# ProPrj___2024-07-22_15-28-46_2024-09-27.net
KiCad netlist of a schematic drawn in EasyEDA Pro
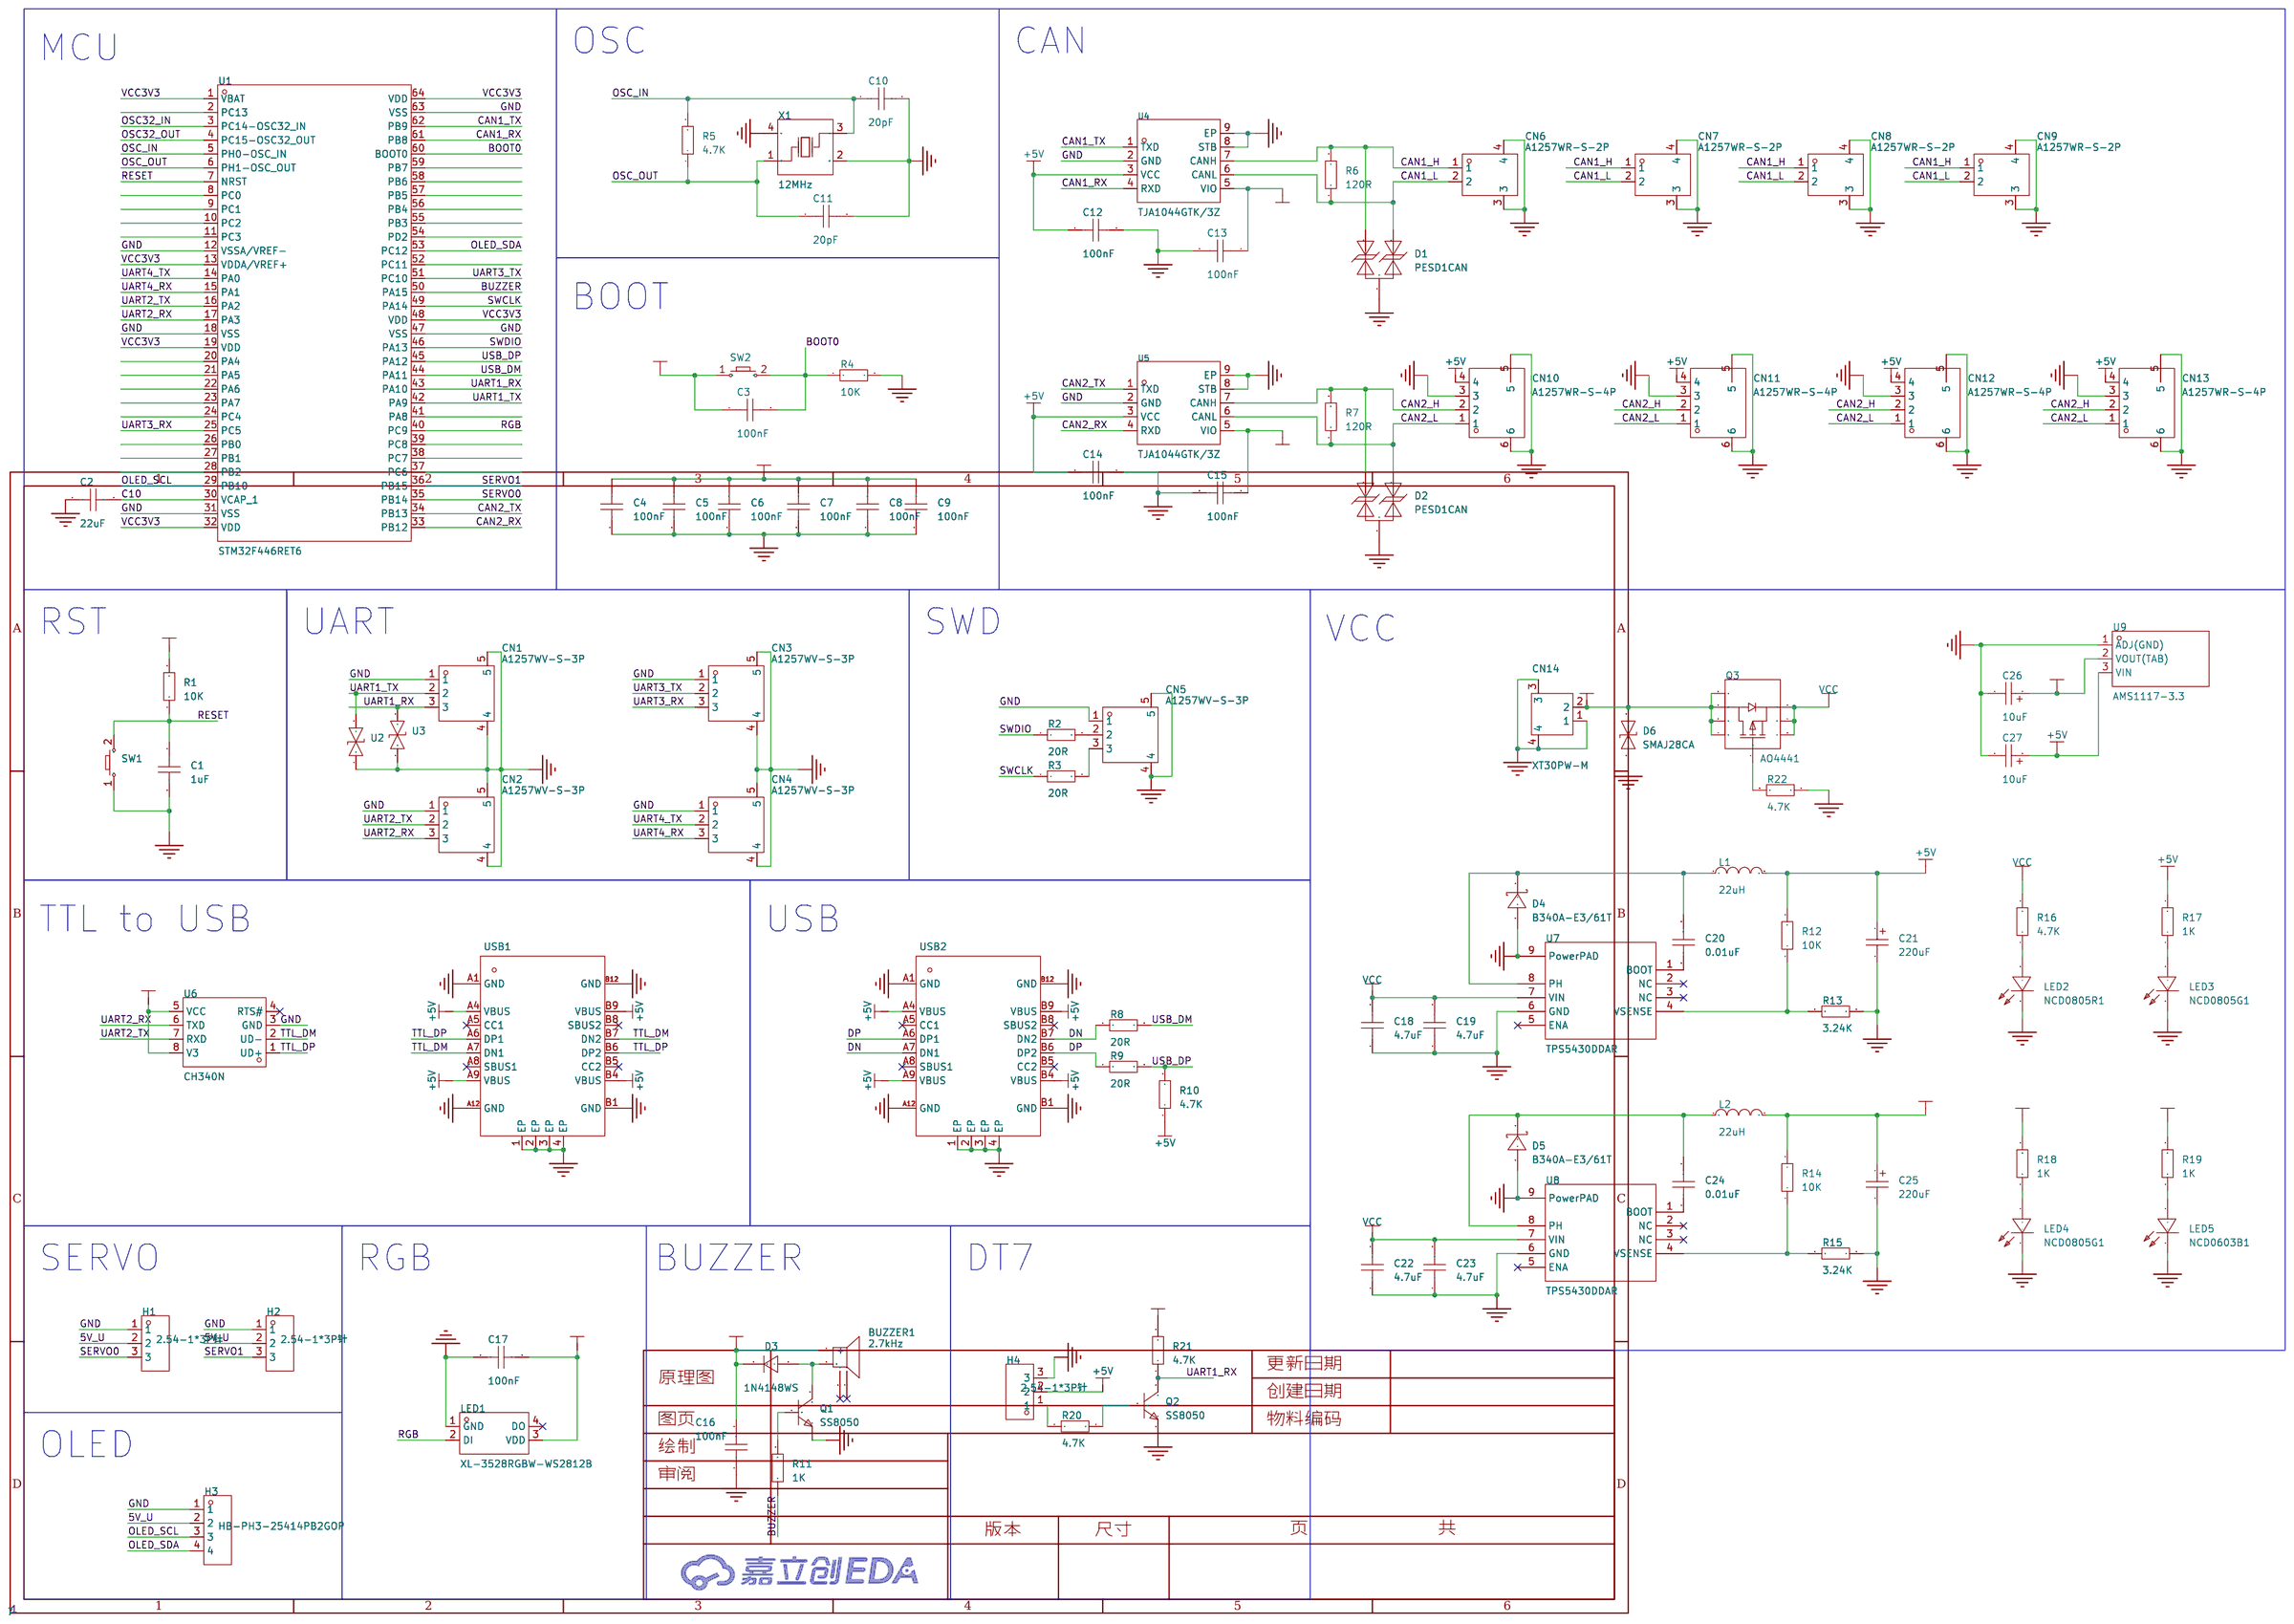
[diagram p0: schematic sheet]

(export (version "E")
  (design (tool "Eeschema 10.0.6"))
  (components
    (comp (ref "BUZZER1")
      (value "2.7kHz")
      (footprint "easyedapro:BUZ-SMD_4P-L8.5-W8.5-P8.50-BR")
      (description "驱动方式:无源(外部驱动);构造类型:电磁式;频率:2.7kHz;声压(SPL):80dB@5V,10cm;")
      (fields (field (name "Manufacturer Part") "MLT-8530") (field (name "Manufacturer") "华能"))
      (libsource (lib "easyedapro") (part "MLT-8530"))
    )
    (comp (ref "C1")
      (value "1uF")
      (footprint "easyedapro:C0603")
      (libsource (lib "easyedapro") (part "CapAcitance"))
    )
    (comp (ref "C2")
      (value "22uF")
      (footprint "easyedapro:C0603")
      (libsource (lib "easyedapro") (part "CapAcitance"))
    )
    (comp (ref "C3")
      (value "100nF")
      (footprint "easyedapro:C0603")
      (libsource (lib "easyedapro") (part "CapAcitance"))
    )
    (comp (ref "C4")
      (value "100nF")
      (footprint "easyedapro:C0603")
      (libsource (lib "easyedapro") (part "CapAcitance"))
    )
    (comp (ref "C5")
      (value "100nF")
      (footprint "easyedapro:C0603")
      (libsource (lib "easyedapro") (part "CapAcitance"))
    )
    (comp (ref "C6")
      (value "100nF")
      (footprint "easyedapro:C0603")
      (libsource (lib "easyedapro") (part "CapAcitance"))
    )
    (comp (ref "C7")
      (value "100nF")
      (footprint "easyedapro:C0603")
      (libsource (lib "easyedapro") (part "CapAcitance"))
    )
    (comp (ref "C8")
      (value "100nF")
      (footprint "easyedapro:C0603")
      (libsource (lib "easyedapro") (part "CapAcitance"))
    )
    (comp (ref "C9")
      (value "100nF")
      (footprint "easyedapro:C0603")
      (libsource (lib "easyedapro") (part "CapAcitance"))
    )
    (comp (ref "C10")
      (value "20pF")
      (footprint "easyedapro:C0603")
      (libsource (lib "easyedapro") (part "CapAcitance"))
    )
    (comp (ref "C11")
      (value "20pF")
      (footprint "easyedapro:C0603")
      (libsource (lib "easyedapro") (part "CapAcitance"))
    )
    (comp (ref "C12")
      (value "100nF")
      (footprint "easyedapro:C0603")
      (libsource (lib "easyedapro") (part "CapAcitance"))
    )
    (comp (ref "C13")
      (value "100nF")
      (footprint "easyedapro:C0603")
      (libsource (lib "easyedapro") (part "CapAcitance"))
    )
    (comp (ref "C14")
      (value "100nF")
      (footprint "easyedapro:C0603")
      (libsource (lib "easyedapro") (part "CapAcitance"))
    )
    (comp (ref "C15")
      (value "100nF")
      (footprint "easyedapro:C0603")
      (libsource (lib "easyedapro") (part "CapAcitance"))
    )
    (comp (ref "C16")
      (value "100nF")
      (footprint "easyedapro:C0603")
      (libsource (lib "easyedapro") (part "CapAcitance"))
    )
    (comp (ref "C17")
      (value "100nF")
      (footprint "easyedapro:C0603")
      (libsource (lib "easyedapro") (part "CapAcitance"))
    )
    (comp (ref "C18")
      (value "4.7uF")
      (footprint "easyedapro:C0603")
      (libsource (lib "easyedapro") (part "CapAcitance"))
    )
    (comp (ref "C19")
      (value "4.7uF")
      (footprint "easyedapro:C0603")
      (libsource (lib "easyedapro") (part "CapAcitance"))
    )
    (comp (ref "C20")
      (value "0.01uF")
      (footprint "easyedapro:C0603")
      (libsource (lib "easyedapro") (part "CapAcitance"))
    )
    (comp (ref "C21")
      (value "220uF")
      (footprint "easyedapro:C_Ele_SMD_5x5.4mm")
      (libsource (lib "easyedapro") (part "CAP"))
    )
    (comp (ref "C22")
      (value "4.7uF")
      (footprint "easyedapro:C0603")
      (libsource (lib "easyedapro") (part "CapAcitance"))
    )
    (comp (ref "C23")
      (value "4.7uF")
      (footprint "easyedapro:C0603")
      (libsource (lib "easyedapro") (part "CapAcitance"))
    )
    (comp (ref "C24")
      (value "0.01uF")
      (footprint "easyedapro:C0603")
      (libsource (lib "easyedapro") (part "CapAcitance"))
    )
    (comp (ref "C25")
      (value "220uF")
      (footprint "easyedapro:C_Ele_SMD_5x5.4mm")
      (libsource (lib "easyedapro") (part "CAP"))
    )
    (comp (ref "C26")
      (value "10uF")
      (footprint "easyedapro:C_Ele_SMD_5x5.4mm")
      (libsource (lib "easyedapro") (part "CAP"))
    )
    (comp (ref "C27")
      (value "10uF")
      (footprint "easyedapro:C_Ele_SMD_5x5.4mm")
      (libsource (lib "easyedapro") (part "CAP"))
    )
    (comp (ref "CN1")
      (value "A1257WV-S-3P")
      (footprint "easyedapro:CONN-SMD_A1257WV-S-3P")
      (description "插针结构:1x3P;间距:1.25mm;安装方式:-;参考系列:GH;总PIN数:3P;排数:1;每排PIN数:3;行距:-;触头材质:黄铜;")
      (fields (field (name "Manufacturer") "CJT(长江连接器)"))
      (libsource (lib "easyedapro") (part "A1257WV-S-3P"))
    )
    (comp (ref "CN2")
      (value "A1257WV-S-3P")
      (footprint "easyedapro:CONN-SMD_A1257WV-S-3P")
      (description "插针结构:1x3P;间距:1.25mm;安装方式:-;参考系列:GH;总PIN数:3P;排数:1;每排PIN数:3;行距:-;触头材质:黄铜;")
      (fields (field (name "Manufacturer") "CJT(长江连接器)"))
      (libsource (lib "easyedapro") (part "A1257WV-S-3P"))
    )
    (comp (ref "CN3")
      (value "A1257WV-S-3P")
      (footprint "easyedapro:CONN-SMD_A1257WV-S-3P")
      (description "插针结构:1x3P;间距:1.25mm;安装方式:-;参考系列:GH;总PIN数:3P;排数:1;每排PIN数:3;行距:-;触头材质:黄铜;")
      (fields (field (name "Manufacturer") "CJT(长江连接器)"))
      (libsource (lib "easyedapro") (part "A1257WV-S-3P"))
    )
    (comp (ref "CN4")
      (value "A1257WV-S-3P")
      (footprint "easyedapro:CONN-SMD_A1257WV-S-3P")
      (description "插针结构:1x3P;间距:1.25mm;安装方式:-;参考系列:GH;总PIN数:3P;排数:1;每排PIN数:3;行距:-;触头材质:黄铜;")
      (fields (field (name "Manufacturer") "CJT(长江连接器)"))
      (libsource (lib "easyedapro") (part "A1257WV-S-3P"))
    )
    (comp (ref "CN5")
      (value "A1257WV-S-3P")
      (footprint "easyedapro:CONN-SMD_A1257WV-S-3P")
      (description "插针结构:1x3P;间距:1.25mm;安装方式:-;参考系列:GH;总PIN数:3P;排数:1;每排PIN数:3;行距:-;触头材质:黄铜;")
      (fields (field (name "Manufacturer") "CJT(长江连接器)"))
      (libsource (lib "easyedapro") (part "A1257WV-S-3P"))
    )
    (comp (ref "CN6")
      (value "A1257WR-S-2P")
      (footprint "easyedapro:CONN-SMD_A1257WR-S-2P")
      (description "插针结构:1x2P;间距:1.25mm;安装方式:-;参考系列:GH;总PIN数:2P;排数:1;每排PIN数:2;行距:-;触头材质:黄铜;")
      (fields (field (name "Manufacturer") "CJT(长江连接器)"))
      (libsource (lib "easyedapro") (part "A1257WR-S-2P"))
    )
    (comp (ref "CN7")
      (value "A1257WR-S-2P")
      (footprint "easyedapro:CONN-SMD_A1257WR-S-2P")
      (description "插针结构:1x2P;间距:1.25mm;安装方式:-;参考系列:GH;总PIN数:2P;排数:1;每排PIN数:2;行距:-;触头材质:黄铜;")
      (fields (field (name "Manufacturer") "CJT(长江连接器)"))
      (libsource (lib "easyedapro") (part "A1257WR-S-2P"))
    )
    (comp (ref "CN8")
      (value "A1257WR-S-2P")
      (footprint "easyedapro:CONN-SMD_A1257WR-S-2P")
      (description "插针结构:1x2P;间距:1.25mm;安装方式:-;参考系列:GH;总PIN数:2P;排数:1;每排PIN数:2;行距:-;触头材质:黄铜;")
      (fields (field (name "Manufacturer") "CJT(长江连接器)"))
      (libsource (lib "easyedapro") (part "A1257WR-S-2P"))
    )
    (comp (ref "CN9")
      (value "A1257WR-S-2P")
      (footprint "easyedapro:CONN-SMD_A1257WR-S-2P")
      (description "插针结构:1x2P;间距:1.25mm;安装方式:-;参考系列:GH;总PIN数:2P;排数:1;每排PIN数:2;行距:-;触头材质:黄铜;")
      (fields (field (name "Manufacturer") "CJT(长江连接器)"))
      (libsource (lib "easyedapro") (part "A1257WR-S-2P"))
    )
    (comp (ref "CN10")
      (value "A1257WR-S-4P")
      (footprint "easyedapro:CONN-SMD_A1257WR-S-4P")
      (description "插针结构:1x4P;间距:1.25mm;安装方式:-;参考系列:GH;总PIN数:4P;排数:1;每排PIN数:4;行距:-;触头材质:黄铜;")
      (fields (field (name "Manufacturer") "CJT(长江连接器)"))
      (libsource (lib "easyedapro") (part "A1257WR-S-4P"))
    )
    (comp (ref "CN11")
      (value "A1257WR-S-4P")
      (footprint "easyedapro:CONN-SMD_A1257WR-S-4P")
      (description "插针结构:1x4P;间距:1.25mm;安装方式:-;参考系列:GH;总PIN数:4P;排数:1;每排PIN数:4;行距:-;触头材质:黄铜;")
      (fields (field (name "Manufacturer") "CJT(长江连接器)"))
      (libsource (lib "easyedapro") (part "A1257WR-S-4P"))
    )
    (comp (ref "CN12")
      (value "A1257WR-S-4P")
      (footprint "easyedapro:CONN-SMD_A1257WR-S-4P")
      (description "插针结构:1x4P;间距:1.25mm;安装方式:-;参考系列:GH;总PIN数:4P;排数:1;每排PIN数:4;行距:-;触头材质:黄铜;")
      (fields (field (name "Manufacturer") "CJT(长江连接器)"))
      (libsource (lib "easyedapro") (part "A1257WR-S-4P"))
    )
    (comp (ref "CN13")
      (value "A1257WR-S-4P")
      (footprint "easyedapro:CONN-SMD_A1257WR-S-4P")
      (description "插针结构:1x4P;间距:1.25mm;安装方式:-;参考系列:GH;总PIN数:4P;排数:1;每排PIN数:4;行距:-;触头材质:黄铜;")
      (fields (field (name "Manufacturer") "CJT(长江连接器)"))
      (libsource (lib "easyedapro") (part "A1257WR-S-4P"))
    )
    (comp (ref "CN14")
      (value "XT30PW-M")
      (footprint "easyedapro:CONN-TH_XT30PW-M")
      (description "类别:-;类型1:-;")
      (fields (field (name "Manufacturer") "AMASS(艾迈斯)"))
      (libsource (lib "easyedapro") (part "XT30PW-M"))
    )
    (comp (ref "D1")
      (value "PESD1CAN")
      (footprint "easyedapro:SOT-23-3_L2.9-W1.6-P1.90-LS2.8-BR")
      (description "极性:双向;反向截止电压(Vrwm):24V;最大钳位电压:48V;峰值脉冲电流(Ipp)@10/1000us:6A;击穿电压:26.7V;")
      (fields (field (name "Manufacturer") "BORN(伯恩半导体)"))
      (libsource (lib "easyedapro") (part "PESD1CAN_C343993"))
    )
    (comp (ref "D2")
      (value "PESD1CAN")
      (footprint "easyedapro:SOT-23-3_L2.9-W1.6-P1.90-LS2.8-BR")
      (description "极性:双向;反向截止电压(Vrwm):24V;最大钳位电压:48V;峰值脉冲电流(Ipp)@10/1000us:6A;击穿电压:26.7V;")
      (fields (field (name "Manufacturer") "BORN(伯恩半导体)"))
      (libsource (lib "easyedapro") (part "PESD1CAN_C343993"))
    )
    (comp (ref "D3")
      (value "1N4148WS")
      (footprint "easyedapro:SOD-323_L1.8-W1.3-LS2.5-RD")
      (description "二极管配置:独立式;正向压降(Vf):1.25V@150mA;直流反向耐压(Vr):100V;平均整流电流(Io):150mA;功率:200mW;反向恢复时间(trr):4ns;")
      (fields (field (name "Manufacturer") "CJ(江苏长电/长晶)"))
      (libsource (lib "easyedapro") (part "1N4148WS T4"))
    )
    (comp (ref "D4")
      (value "B340A-E3/61T")
      (footprint "easyedapro:SMA_L4.3-W2.6-LS5.2-RD")
      (description "正向压降(Vf):550mV@3A;直流反向耐压(Vr):40V;平均整流电流(Io):3A;")
      (fields (field (name "Manufacturer") "VISHAY(威世)"))
      (libsource (lib "easyedapro") (part "B340A-E3/61T"))
    )
    (comp (ref "D5")
      (value "B340A-E3/61T")
      (footprint "easyedapro:SMA_L4.3-W2.6-LS5.2-RD")
      (description "正向压降(Vf):550mV@3A;直流反向耐压(Vr):40V;平均整流电流(Io):3A;")
      (fields (field (name "Manufacturer") "VISHAY(威世)"))
      (libsource (lib "easyedapro") (part "B340A-E3/61T"))
    )
    (comp (ref "D6")
      (value "SMAJ28CA")
      (footprint "easyedapro:SMA_L4.4-W2.6-LS5.0-BI")
      (description "反向截止电压(Vrwm):28V;最大钳位电压:45.4V;峰值脉冲电流(Ipp)@10/1000us:8.8A;峰值脉冲功率(Ppp)@10/1000us:400W;击穿电压:31.1V;")
      (fields (field (name "Manufacturer") "Littelfuse(美国力特)"))
      (libsource (lib "easyedapro") (part "SMAJ28CA-C148228"))
    )
    (comp (ref "H1")
      (value "2.54-1*3P针")
      (footprint "easyedapro:HDR-TH_3P-P2.54-V-F")
      (fields (field (name "Manufacturer") "BOOMELE(博穆精密)"))
      (libsource (lib "easyedapro") (part "PM254V-11-03-H85"))
    )
    (comp (ref "H2")
      (value "2.54-1*3P针")
      (footprint "easyedapro:HDR-TH_3P-P2.54-V-F")
      (fields (field (name "Manufacturer") "BOOMELE(博穆精密)"))
      (libsource (lib "easyedapro") (part "PM254V-11-03-H85"))
    )
    (comp (ref "H3")
      (value "HB-PH3-25414PB2GOP")
      (footprint "easyedapro:HDR-TH_4P-P2.54-V-F")
      (fields (field (name "Manufacturer") "HANBO(汉博)"))
      (libsource (lib "easyedapro") (part "2.54-1*4P母"))
    )
    (comp (ref "H4")
      (value "2.54-1*3P针")
      (footprint "easyedapro:HDR-TH_3P-P2.54-V-F")
      (fields (field (name "Manufacturer") "BOOMELE(博穆精密)"))
      (libsource (lib "easyedapro") (part "PM254V-11-03-H85"))
    )
    (comp (ref "L1")
      (value "22uH")
      (footprint "easyedapro:L0603")
      (libsource (lib "easyedapro") (part "SDFL1608S100KTF"))
    )
    (comp (ref "L2")
      (value "22uH")
      (footprint "easyedapro:L0603")
      (libsource (lib "easyedapro") (part "SDFL1608S100KTF"))
    )
    (comp (ref "LED1")
      (value "XL-3528RGBW-WS2812B")
      (footprint "easyedapro:LED-SMD_4P-L3.5-W2.8-BR-1")
      (description "3528 七彩幻彩雾状 ws2812B 内置驱动IC")
      (fields (field (name "Manufacturer") "XINGLIGHT(成兴光)"))
      (libsource (lib "easyedapro") (part "XL-3528RGBW-WS2812B"))
    )
    (comp (ref "LED2")
      (value "NCD0805R1")
      (footprint "easyedapro:LED0805-R-RD")
      (fields (field (name "Manufacturer") "国星光电"))
      (libsource (lib "easyedapro") (part "FC-2012HRK-620D"))
    )
    (comp (ref "LED3")
      (value "NCD0805G1")
      (footprint "easyedapro:LED0805-R-RD")
      (fields (field (name "Manufacturer") "国星光电"))
      (libsource (lib "easyedapro") (part "FC-2012HRK-620D"))
    )
    (comp (ref "LED4")
      (value "NCD0805G1")
      (footprint "easyedapro:LED0805-R-RD")
      (fields (field (name "Manufacturer") "国星光电"))
      (libsource (lib "easyedapro") (part "FC-2012HRK-620D"))
    )
    (comp (ref "LED5")
      (value "NCD0603B1")
      (footprint "easyedapro:LED0805-R-RD")
      (fields (field (name "Manufacturer") "国星光电"))
      (libsource (lib "easyedapro") (part "FC-2012HRK-620D"))
    )
    (comp (ref "Q1")
      (value "SS8050")
      (footprint "easyedapro:SOT-23-3_L2.9-W1.3-P1.90-LS2.4-BR")
      (description "晶体管类型:NPN;集电极电流(Ic):1.5A;集射极击穿电压(Vceo):25V;功率(Pd):300mW;直流电流增益(hFE@Ic,Vce):200@100mA,1V;")
      (fields (field (name "Manufacturer") "CJ(江苏长电/长晶)"))
      (libsource (lib "easyedapro") (part "SS8050_C2150"))
    )
    (comp (ref "Q2")
      (value "SS8050")
      (footprint "easyedapro:SOT-23-3_L2.9-W1.3-P1.90-LS2.4-BR")
      (description "晶体管类型:NPN;集电极电流(Ic):1.5A;集射极击穿电压(Vceo):25V;功率(Pd):300mW;直流电流增益(hFE@Ic,Vce):200@100mA,1V;")
      (fields (field (name "Manufacturer") "CJ(江苏长电/长晶)"))
      (libsource (lib "easyedapro") (part "SS8050_C2150"))
    )
    (comp (ref "Q3")
      (value "AO4441")
      (footprint "easyedapro:SOIC-8_L4.9-W3.9-P1.27-LS6.0-BL")
      (fields (field (name "Manufacturer") "AOS"))
      (libsource (lib "easyedapro") (part "AO4441"))
    )
    (comp (ref "R1") (value "10K") (footprint "easyedapro:R0603") (libsource (lib "easyedapro") (part "电阻")))
    (comp (ref "R2") (value "20R") (footprint "easyedapro:R0603") (libsource (lib "easyedapro") (part "电阻")))
    (comp (ref "R3") (value "20R") (footprint "easyedapro:R0603") (libsource (lib "easyedapro") (part "电阻")))
    (comp (ref "R4") (value "10K") (footprint "easyedapro:R0603") (libsource (lib "easyedapro") (part "电阻")))
    (comp (ref "R5") (value "4.7K") (footprint "easyedapro:R0603") (libsource (lib "easyedapro") (part "电阻")))
    (comp (ref "R6") (value "120R") (footprint "easyedapro:R0603") (libsource (lib "easyedapro") (part "电阻")))
    (comp (ref "R7") (value "120R") (footprint "easyedapro:R0603") (libsource (lib "easyedapro") (part "电阻")))
    (comp (ref "R8") (value "20R") (footprint "easyedapro:R0603") (libsource (lib "easyedapro") (part "电阻")))
    (comp (ref "R9") (value "20R") (footprint "easyedapro:R0603") (libsource (lib "easyedapro") (part "电阻")))
    (comp (ref "R10")
      (value "4.7K")
      (footprint "easyedapro:R0603")
      (libsource (lib "easyedapro") (part "电阻"))
    )
    (comp (ref "R11") (value "1K") (footprint "easyedapro:R0603") (libsource (lib "easyedapro") (part "电阻")))
    (comp (ref "R12") (value "10K") (footprint "easyedapro:R0603") (libsource (lib "easyedapro") (part "电阻")))
    (comp (ref "R13")
      (value "3.24K")
      (footprint "easyedapro:R0603")
      (libsource (lib "easyedapro") (part "电阻"))
    )
    (comp (ref "R14") (value "10K") (footprint "easyedapro:R0603") (libsource (lib "easyedapro") (part "电阻")))
    (comp (ref "R15")
      (value "3.24K")
      (footprint "easyedapro:R0603")
      (libsource (lib "easyedapro") (part "电阻"))
    )
    (comp (ref "R16")
      (value "4.7K")
      (footprint "easyedapro:R0603")
      (libsource (lib "easyedapro") (part "电阻"))
    )
    (comp (ref "R17") (value "1K") (footprint "easyedapro:R0603") (libsource (lib "easyedapro") (part "电阻")))
    (comp (ref "R18") (value "1K") (footprint "easyedapro:R0603") (libsource (lib "easyedapro") (part "电阻")))
    (comp (ref "R19") (value "1K") (footprint "easyedapro:R0603") (libsource (lib "easyedapro") (part "电阻")))
    (comp (ref "R20")
      (value "4.7K")
      (footprint "easyedapro:R0603")
      (libsource (lib "easyedapro") (part "电阻"))
    )
    (comp (ref "R21")
      (value "4.7K")
      (footprint "easyedapro:R0603")
      (libsource (lib "easyedapro") (part "电阻"))
    )
    (comp (ref "R22")
      (value "4.7K")
      (footprint "easyedapro:R0603")
      (libsource (lib "easyedapro") (part "电阻"))
    )
    (comp (ref "SW1")
      (value "~")
      (footprint "easyedapro:Key_SMD_3x4x2")
      (libsource (lib "easyedapro") (part "轻触按键x2"))
    )
    (comp (ref "SW2")
      (value "~")
      (footprint "easyedapro:Key_SMD_3x4x2")
      (libsource (lib "easyedapro") (part "轻触按键x2"))
    )
    (comp (ref "U1")
      (value "STM32F446RET6")
      (footprint "easyedapro:LQFP-64_L10.0-W10.0-P0.50-LS12.0-BL")
      (description "CPU内核:CM4;程序存储容量:512KB;RAM总容量:128KB;GPIO端口数量:50;工作电压范围:1.7V~3.6V;CPU最大主频:180MHz;程序存储器类型:FLASH;")
      (fields (field (name "Manufacturer") "ST(意法半导体)"))
      (libsource (lib "easyedapro") (part "STM32F446RET6"))
    )
    (comp (ref "U2")
      (value "ESD9B5.0ST5G")
      (footprint "easyedapro:SOD-923_L0.8-W0.6-LS1.0-BI")
      (fields (field (name "Manufacturer") "TECH PUBLIC(台舟)"))
      (libsource (lib "easyedapro") (part "ESD9B5.0ST5G_C3021104"))
    )
    (comp (ref "U3")
      (value "ESD9B5.0ST5G")
      (footprint "easyedapro:SOD-923_L0.8-W0.6-LS1.0-BI")
      (fields (field (name "Manufacturer") "TECH PUBLIC(台舟)"))
      (libsource (lib "easyedapro") (part "ESD9B5.0ST5G_C3021104"))
    )
    (comp (ref "U4")
      (value "TJA1044GTK/3Z")
      (footprint "easyedapro:HVSON-8_L3.0-W3.0-P0.65-BL-EP")
      (description "类型:-;")
      (fields (field (name "Manufacturer") "NXP(恩智浦)"))
      (libsource (lib "easyedapro") (part "TJA1044GTK/3Z"))
    )
    (comp (ref "U5")
      (value "TJA1044GTK/3Z")
      (footprint "easyedapro:HVSON-8_L3.0-W3.0-P0.65-BL-EP")
      (description "类型:-;")
      (fields (field (name "Manufacturer") "NXP(恩智浦)"))
      (libsource (lib "easyedapro") (part "TJA1044GTK/3Z"))
    )
    (comp (ref "U6")
      (value "CH340N")
      (footprint "easyedapro:SOP-8_L4.9-W3.9-P1.27-LS6.0-BL")
      (fields (field (name "Manufacturer") "WCH(南京沁恒)"))
      (libsource (lib "easyedapro") (part "CH340N_C2977777"))
    )
    (comp (ref "U7")
      (value "TPS5430DDAR")
      (footprint "easyedapro:ESOP-8_L4.9-W3.9-P1.27-LS6.0-TL-EP")
      (description "功能类型:降压型;输出类型:可调;输入电压:5.5V~36V;输出电压:1.221V~32.04V;输出电流(最大值):3A;")
      (fields (field (name "Manufacturer") "TI(德州仪器)"))
      (libsource (lib "easyedapro") (part "TPS5430DDAR"))
    )
    (comp (ref "U8")
      (value "TPS5430DDAR")
      (footprint "easyedapro:ESOP-8_L4.9-W3.9-P1.27-LS6.0-TL-EP")
      (description "功能类型:降压型;输出类型:可调;输入电压:5.5V~36V;输出电压:1.221V~32.04V;输出电流(最大值):3A;")
      (fields (field (name "Manufacturer") "TI(德州仪器)"))
      (libsource (lib "easyedapro") (part "TPS5430DDAR"))
    )
    (comp (ref "U9")
      (value "AMS1117-3.3")
      (footprint "easyedapro:SOT-89_L4.5-W2.5-P1.50-LS4.2-BR")
      (description "输出类型:固定;最大输入电压:12V;输出电压:3.3V;最大输出电流:1A;电源纹波抑制比(PSRR):60dB@(120Hz);输出极性:正极;")
      (fields (field (name "Manufacturer") "UMW(友台半导体)"))
      (libsource (lib "easyedapro") (part "AMS1117-3.3_C347256"))
    )
    (comp (ref "USB1")
      (value "~")
      (footprint "easyedapro:USB_TYPE-C-16P")
      (libsource (lib "easyedapro") (part "USB_TYPE-C-16P"))
    )
    (comp (ref "USB2")
      (value "~")
      (footprint "easyedapro:USB_TYPE-C-16P")
      (libsource (lib "easyedapro") (part "USB_TYPE-C-16P"))
    )
    (comp (ref "X1")
      (value "12MHz")
      (footprint "easyedapro:OSC-SMD_4P-L3.2-W2.5-BL")
      (description "晶振类型:贴片晶振;频率:12MHz;常温频差:±10ppm;外接负载电容:20pF;频率稳定度(全温):±20ppm;")
      (fields (field (name "Manufacturer Part") "X322512MSB4SI") (field (name "Manufacturer") "YXC(扬兴晶振)"))
      (libsource (lib "easyedapro") (part "X322512MSB4SI"))
    )
  )
  (nets
    (net (code "1") (name "+5V") (class "Default")
      (node (ref "C12") (pin "2") (pinfunction "2_2") (pintype "input"))
      (node (ref "C14") (pin "2") (pinfunction "2_2") (pintype "input"))
      (node (ref "C21") (pin "1") (pinfunction "1_1") (pintype "input"))
      (node (ref "C27") (pin "1") (pinfunction "1_1") (pintype "input"))
      (node (ref "CN10") (pin "4") (pinfunction "4_4") (pintype "unspecified"))
      (node (ref "CN11") (pin "4") (pinfunction "4_4") (pintype "unspecified"))
      (node (ref "CN12") (pin "4") (pinfunction "4_4") (pintype "unspecified"))
      (node (ref "CN13") (pin "4") (pinfunction "4_4") (pintype "unspecified"))
      (node (ref "H4") (pin "2") (pinfunction "2_2") (pintype "unspecified"))
      (node (ref "L1") (pin "2") (pinfunction "2_2") (pintype "unspecified"))
      (node (ref "R10") (pin "1") (pinfunction "1_1") (pintype "input"))
      (node (ref "R12") (pin "2") (pinfunction "2_2") (pintype "input"))
      (node (ref "R17") (pin "2") (pinfunction "2_2") (pintype "input"))
      (node (ref "U4") (pin "3") (pinfunction "VCC_3") (pintype "input"))
      (node (ref "U5") (pin "3") (pinfunction "VCC_3") (pintype "input"))
      (node (ref "U9") (pin "3") (pinfunction "VIN_3") (pintype "unspecified"))
      (node (ref "USB1") (pin "A4") (pinfunction "VBUS_A4") (pintype "input"))
      (node (ref "USB1") (pin "A9") (pinfunction "VBUS_A9") (pintype "input"))
      (node (ref "USB1") (pin "B4") (pinfunction "VBUS_B4") (pintype "input"))
      (node (ref "USB1") (pin "B9") (pinfunction "VBUS_B9") (pintype "input"))
      (node (ref "USB2") (pin "A4") (pinfunction "VBUS_A4") (pintype "input"))
      (node (ref "USB2") (pin "A9") (pinfunction "VBUS_A9") (pintype "input"))
      (node (ref "USB2") (pin "B4") (pinfunction "VBUS_B4") (pintype "input"))
      (node (ref "USB2") (pin "B9") (pinfunction "VBUS_B9") (pintype "input"))
    )
    (net (code "2") (name "/BOOT0") (class "Default")
      (node (ref "C3") (pin "2") (pinfunction "2_2") (pintype "input"))
      (node (ref "R4") (pin "1") (pinfunction "1_1") (pintype "input"))
      (node (ref "SW2") (pin "2") (pinfunction "2_2") (pintype "input"))
      (node (ref "U1") (pin "60") (pinfunction "BOOT0_60") (pintype "unspecified"))
    )
    (net (code "3") (name "/BUZZER") (class "Default")
      (node (ref "R11") (pin "1") (pinfunction "1_1") (pintype "input"))
      (node (ref "U1") (pin "50") (pinfunction "PA15_50") (pintype "unspecified"))
    )
    (net (code "4") (name "/C10") (class "Default")
      (node (ref "C2") (pin "2") (pinfunction "2_2") (pintype "input"))
      (node (ref "U1") (pin "30") (pinfunction "VCAP_1_30") (pintype "unspecified"))
    )
    (net (code "5") (name "/CAN1_H") (class "Default")
      (node (ref "CN6") (pin "1") (pinfunction "1_1") (pintype "unspecified"))
      (node (ref "CN7") (pin "1") (pinfunction "1_1") (pintype "unspecified"))
      (node (ref "CN8") (pin "1") (pinfunction "1_1") (pintype "unspecified"))
      (node (ref "CN9") (pin "1") (pinfunction "1_1") (pintype "unspecified"))
      (node (ref "D1") (pin "2") (pinfunction "K_2") (pintype "unspecified"))
      (node (ref "R6") (pin "2") (pinfunction "2_2") (pintype "input"))
      (node (ref "U4") (pin "7") (pinfunction "CANH_7") (pintype "input"))
    )
    (net (code "6") (name "/CAN1_L") (class "Default")
      (node (ref "CN6") (pin "2") (pinfunction "2_2") (pintype "unspecified"))
      (node (ref "CN7") (pin "2") (pinfunction "2_2") (pintype "unspecified"))
      (node (ref "CN8") (pin "2") (pinfunction "2_2") (pintype "unspecified"))
      (node (ref "CN9") (pin "2") (pinfunction "2_2") (pintype "unspecified"))
      (node (ref "D1") (pin "1") (pinfunction "K_1") (pintype "unspecified"))
      (node (ref "R6") (pin "1") (pinfunction "1_1") (pintype "input"))
      (node (ref "U4") (pin "6") (pinfunction "CANL_6") (pintype "input"))
    )
    (net (code "7") (name "/CAN1_RX") (class "Default")
      (node (ref "U1") (pin "61") (pinfunction "PB8_61") (pintype "unspecified"))
      (node (ref "U4") (pin "4") (pinfunction "RXD_4") (pintype "input"))
    )
    (net (code "8") (name "/CAN1_TX") (class "Default")
      (node (ref "U1") (pin "62") (pinfunction "PB9_62") (pintype "unspecified"))
      (node (ref "U4") (pin "1") (pinfunction "TXD_1") (pintype "input"))
    )
    (net (code "9") (name "/CAN2_H") (class "Default")
      (node (ref "CN10") (pin "2") (pinfunction "2_2") (pintype "unspecified"))
      (node (ref "CN11") (pin "2") (pinfunction "2_2") (pintype "unspecified"))
      (node (ref "CN12") (pin "2") (pinfunction "2_2") (pintype "unspecified"))
      (node (ref "CN13") (pin "2") (pinfunction "2_2") (pintype "unspecified"))
      (node (ref "D2") (pin "2") (pinfunction "K_2") (pintype "unspecified"))
      (node (ref "R7") (pin "2") (pinfunction "2_2") (pintype "input"))
      (node (ref "U5") (pin "7") (pinfunction "CANH_7") (pintype "input"))
    )
    (net (code "10") (name "/CAN2_L") (class "Default")
      (node (ref "CN10") (pin "1") (pinfunction "1_1") (pintype "unspecified"))
      (node (ref "CN11") (pin "1") (pinfunction "1_1") (pintype "unspecified"))
      (node (ref "CN12") (pin "1") (pinfunction "1_1") (pintype "unspecified"))
      (node (ref "CN13") (pin "1") (pinfunction "1_1") (pintype "unspecified"))
      (node (ref "D2") (pin "1") (pinfunction "K_1") (pintype "unspecified"))
      (node (ref "R7") (pin "1") (pinfunction "1_1") (pintype "input"))
      (node (ref "U5") (pin "6") (pinfunction "CANL_6") (pintype "input"))
    )
    (net (code "11") (name "/CAN2_RX") (class "Default")
      (node (ref "U1") (pin "33") (pinfunction "PB12_33") (pintype "unspecified"))
      (node (ref "U5") (pin "4") (pinfunction "RXD_4") (pintype "input"))
    )
    (net (code "12") (name "/CAN2_TX") (class "Default")
      (node (ref "U1") (pin "34") (pinfunction "PB13_34") (pintype "unspecified"))
      (node (ref "U5") (pin "1") (pinfunction "TXD_1") (pintype "input"))
    )
    (net (code "13") (name "/DN") (class "Default")
      (node (ref "R8") (pin "1") (pinfunction "1_1") (pintype "input"))
      (node (ref "USB2") (pin "A7") (pinfunction "DN1_A7") (pintype "input"))
      (node (ref "USB2") (pin "B7") (pinfunction "DN2_B7") (pintype "input"))
    )
    (net (code "14") (name "/DP") (class "Default")
      (node (ref "R9") (pin "1") (pinfunction "1_1") (pintype "input"))
      (node (ref "USB2") (pin "A6") (pinfunction "DP1_A6") (pintype "input"))
      (node (ref "USB2") (pin "B6") (pinfunction "DP2_B6") (pintype "input"))
    )
    (net (code "15") (name "/OLED_SCL") (class "Default")
      (node (ref "H3") (pin "3") (pinfunction "3_3") (pintype "unspecified"))
      (node (ref "U1") (pin "29") (pinfunction "PB10_29") (pintype "unspecified"))
    )
    (net (code "16") (name "/OLED_SDA") (class "Default")
      (node (ref "H3") (pin "4") (pinfunction "4_4") (pintype "unspecified"))
      (node (ref "U1") (pin "53") (pinfunction "PC12_53") (pintype "unspecified"))
    )
    (net (code "17") (name "/OSC32_IN") (class "Default")
      (node (ref "U1") (pin "3") (pinfunction "PC14-OSC32_IN_3") (pintype "unspecified"))
    )
    (net (code "18") (name "/OSC32_OUT") (class "Default")
      (node (ref "U1") (pin "4") (pinfunction "PC15-OSC32_OUT_4") (pintype "unspecified"))
    )
    (net (code "19") (name "/OSC_IN") (class "Default")
      (node (ref "C10") (pin "1") (pinfunction "1_1") (pintype "input"))
      (node (ref "R5") (pin "2") (pinfunction "2_2") (pintype "input"))
      (node (ref "U1") (pin "5") (pinfunction "PH0-OSC_IN_5") (pintype "unspecified"))
      (node (ref "X1") (pin "3") (pinfunction "OSC2_3") (pintype "unspecified"))
    )
    (net (code "20") (name "/OSC_OUT") (class "Default")
      (node (ref "C11") (pin "1") (pinfunction "1_1") (pintype "input"))
      (node (ref "R5") (pin "1") (pinfunction "1_1") (pintype "input"))
      (node (ref "U1") (pin "6") (pinfunction "PH1-OSC_OUT_6") (pintype "unspecified"))
      (node (ref "X1") (pin "1") (pinfunction "OSC1_1") (pintype "unspecified"))
    )
    (net (code "21") (name "/RESET") (class "Default")
      (node (ref "C1") (pin "1") (pinfunction "1_1") (pintype "input"))
      (node (ref "R1") (pin "1") (pinfunction "1_1") (pintype "input"))
      (node (ref "SW1") (pin "2") (pinfunction "2_2") (pintype "input"))
      (node (ref "U1") (pin "7") (pinfunction "NRST_7") (pintype "unspecified"))
    )
    (net (code "22") (name "/RGB") (class "Default")
      (node (ref "LED1") (pin "2") (pinfunction "DI_2") (pintype "unspecified"))
      (node (ref "U1") (pin "40") (pinfunction "PC9_40") (pintype "unspecified"))
    )
    (net (code "23") (name "/SERVO0") (class "Default")
      (node (ref "H1") (pin "3") (pinfunction "3_3") (pintype "unspecified"))
      (node (ref "U1") (pin "35") (pinfunction "PB14_35") (pintype "unspecified"))
    )
    (net (code "24") (name "/SERVO1") (class "Default")
      (node (ref "H2") (pin "3") (pinfunction "3_3") (pintype "unspecified"))
      (node (ref "U1") (pin "36") (pinfunction "PB15_36") (pintype "unspecified"))
    )
    (net (code "25") (name "/SWCLK") (class "Default")
      (node (ref "R3") (pin "1") (pinfunction "1_1") (pintype "input"))
      (node (ref "U1") (pin "49") (pinfunction "PA14_49") (pintype "unspecified"))
    )
    (net (code "26") (name "/SWDIO") (class "Default")
      (node (ref "R2") (pin "1") (pinfunction "1_1") (pintype "input"))
      (node (ref "U1") (pin "46") (pinfunction "PA13_46") (pintype "unspecified"))
    )
    (net (code "27") (name "/TTL_DM") (class "Default")
      (node (ref "U6") (pin "2") (pinfunction "UD-_2") (pintype "unspecified"))
      (node (ref "USB1") (pin "A7") (pinfunction "DN1_A7") (pintype "input"))
      (node (ref "USB1") (pin "B7") (pinfunction "DN2_B7") (pintype "input"))
    )
    (net (code "28") (name "/TTL_DP") (class "Default")
      (node (ref "U6") (pin "1") (pinfunction "UD+_1") (pintype "unspecified"))
      (node (ref "USB1") (pin "A6") (pinfunction "DP1_A6") (pintype "input"))
      (node (ref "USB1") (pin "B6") (pinfunction "DP2_B6") (pintype "input"))
    )
    (net (code "29") (name "/UART1_RX") (class "Default")
      (node (ref "CN1") (pin "3") (pinfunction "3_3") (pintype "unspecified"))
      (node (ref "Q2") (pin "3") (pinfunction "C_3") (pintype "unspecified"))
      (node (ref "R21") (pin "1") (pinfunction "1_1") (pintype "input"))
      (node (ref "U1") (pin "43") (pinfunction "PA10_43") (pintype "unspecified"))
      (node (ref "U3") (pin "2") (pinfunction "2_2") (pintype "unspecified"))
    )
    (net (code "30") (name "/UART1_TX") (class "Default")
      (node (ref "CN1") (pin "2") (pinfunction "2_2") (pintype "unspecified"))
      (node (ref "U1") (pin "42") (pinfunction "PA9_42") (pintype "unspecified"))
      (node (ref "U2") (pin "2") (pinfunction "2_2") (pintype "unspecified"))
    )
    (net (code "31") (name "/UART2_RX") (class "Default")
      (node (ref "CN2") (pin "3") (pinfunction "3_3") (pintype "unspecified"))
      (node (ref "U1") (pin "17") (pinfunction "PA3_17") (pintype "unspecified"))
      (node (ref "U6") (pin "6") (pinfunction "TXD_6") (pintype "unspecified"))
    )
    (net (code "32") (name "/UART2_TX") (class "Default")
      (node (ref "CN2") (pin "2") (pinfunction "2_2") (pintype "unspecified"))
      (node (ref "U1") (pin "16") (pinfunction "PA2_16") (pintype "unspecified"))
      (node (ref "U6") (pin "7") (pinfunction "RXD_7") (pintype "unspecified"))
    )
    (net (code "33") (name "/UART3_RX") (class "Default")
      (node (ref "CN3") (pin "3") (pinfunction "3_3") (pintype "unspecified"))
      (node (ref "U1") (pin "25") (pinfunction "PC5_25") (pintype "unspecified"))
    )
    (net (code "34") (name "/UART3_TX") (class "Default")
      (node (ref "CN3") (pin "2") (pinfunction "2_2") (pintype "unspecified"))
      (node (ref "U1") (pin "51") (pinfunction "PC10_51") (pintype "unspecified"))
    )
    (net (code "35") (name "/UART4_RX") (class "Default")
      (node (ref "CN4") (pin "3") (pinfunction "3_3") (pintype "unspecified"))
      (node (ref "U1") (pin "15") (pinfunction "PA1_15") (pintype "unspecified"))
    )
    (net (code "36") (name "/UART4_TX") (class "Default")
      (node (ref "CN4") (pin "2") (pinfunction "2_2") (pintype "unspecified"))
      (node (ref "U1") (pin "14") (pinfunction "PA0_14") (pintype "unspecified"))
    )
    (net (code "37") (name "/USB_DM") (class "Default")
      (node (ref "R8") (pin "2") (pinfunction "2_2") (pintype "input"))
      (node (ref "U1") (pin "44") (pinfunction "PA11_44") (pintype "unspecified"))
    )
    (net (code "38") (name "/USB_DP") (class "Default")
      (node (ref "R10") (pin "2") (pinfunction "2_2") (pintype "input"))
      (node (ref "R9") (pin "2") (pinfunction "2_2") (pintype "input"))
      (node (ref "U1") (pin "45") (pinfunction "PA12_45") (pintype "unspecified"))
    )
    (net (code "39") (name "5V_U") (class "Default")
      (node (ref "C25") (pin "1") (pinfunction "1_1") (pintype "input"))
      (node (ref "H1") (pin "2") (pinfunction "2_2") (pintype "unspecified"))
      (node (ref "H2") (pin "2") (pinfunction "2_2") (pintype "unspecified"))
      (node (ref "H3") (pin "2") (pinfunction "2_2") (pintype "unspecified"))
      (node (ref "L2") (pin "2") (pinfunction "2_2") (pintype "unspecified"))
      (node (ref "R14") (pin "2") (pinfunction "2_2") (pintype "input"))
      (node (ref "R18") (pin "2") (pinfunction "2_2") (pintype "input"))
    )
    (net (code "40") (name "BAT") (class "Default")
      (node (ref "CN14") (pin "2") (pinfunction "2_2") (pintype "unspecified"))
      (node (ref "D6") (pin "2") (pinfunction "2_2") (pintype "input"))
      (node (ref "Q3") (pin "5") (pinfunction "D_5") (pintype "unspecified"))
      (node (ref "Q3") (pin "6") (pinfunction "D_6") (pintype "unspecified"))
      (node (ref "Q3") (pin "7") (pinfunction "D_7") (pintype "unspecified"))
      (node (ref "Q3") (pin "8") (pinfunction "D_8") (pintype "unspecified"))
    )
    (net (code "41") (name "GND") (class "Default")
      (node (ref "C1") (pin "2") (pinfunction "2_2") (pintype "input"))
      (node (ref "C10") (pin "2") (pinfunction "2_2") (pintype "input"))
      (node (ref "C11") (pin "2") (pinfunction "2_2") (pintype "input"))
      (node (ref "C12") (pin "1") (pinfunction "1_1") (pintype "input"))
      (node (ref "C13") (pin "2") (pinfunction "2_2") (pintype "input"))
      (node (ref "C14") (pin "1") (pinfunction "1_1") (pintype "input"))
      (node (ref "C15") (pin "2") (pinfunction "2_2") (pintype "input"))
      (node (ref "C16") (pin "1") (pinfunction "1_1") (pintype "input"))
      (node (ref "C17") (pin "1") (pinfunction "1_1") (pintype "input"))
      (node (ref "C18") (pin "1") (pinfunction "1_1") (pintype "input"))
      (node (ref "C19") (pin "1") (pinfunction "1_1") (pintype "input"))
      (node (ref "C2") (pin "1") (pinfunction "1_1") (pintype "input"))
      (node (ref "C21") (pin "2") (pinfunction "2_2") (pintype "input"))
      (node (ref "C22") (pin "1") (pinfunction "1_1") (pintype "input"))
      (node (ref "C23") (pin "1") (pinfunction "1_1") (pintype "input"))
      (node (ref "C25") (pin "2") (pinfunction "2_2") (pintype "input"))
      (node (ref "C26") (pin "2") (pinfunction "2_2") (pintype "input"))
      (node (ref "C27") (pin "2") (pinfunction "2_2") (pintype "input"))
      (node (ref "C4") (pin "1") (pinfunction "1_1") (pintype "input"))
      (node (ref "C5") (pin "1") (pinfunction "1_1") (pintype "input"))
      (node (ref "C6") (pin "1") (pinfunction "1_1") (pintype "input"))
      (node (ref "C7") (pin "1") (pinfunction "1_1") (pintype "input"))
      (node (ref "C8") (pin "1") (pinfunction "1_1") (pintype "input"))
      (node (ref "C9") (pin "1") (pinfunction "1_1") (pintype "input"))
      (node (ref "CN1") (pin "1") (pinfunction "1_1") (pintype "unspecified"))
      (node (ref "CN1") (pin "4") (pinfunction "4_4") (pintype "unspecified"))
      (node (ref "CN1") (pin "5") (pinfunction "5_5") (pintype "unspecified"))
      (node (ref "CN10") (pin "3") (pinfunction "3_3") (pintype "unspecified"))
      (node (ref "CN10") (pin "5") (pinfunction "5_5") (pintype "unspecified"))
      (node (ref "CN10") (pin "6") (pinfunction "6_6") (pintype "unspecified"))
      (node (ref "CN11") (pin "3") (pinfunction "3_3") (pintype "unspecified"))
      (node (ref "CN11") (pin "5") (pinfunction "5_5") (pintype "unspecified"))
      (node (ref "CN11") (pin "6") (pinfunction "6_6") (pintype "unspecified"))
      (node (ref "CN12") (pin "3") (pinfunction "3_3") (pintype "unspecified"))
      (node (ref "CN12") (pin "5") (pinfunction "5_5") (pintype "unspecified"))
      (node (ref "CN12") (pin "6") (pinfunction "6_6") (pintype "unspecified"))
      (node (ref "CN13") (pin "3") (pinfunction "3_3") (pintype "unspecified"))
      (node (ref "CN13") (pin "5") (pinfunction "5_5") (pintype "unspecified"))
      (node (ref "CN13") (pin "6") (pinfunction "6_6") (pintype "unspecified"))
      (node (ref "CN14") (pin "1") (pinfunction "1_1") (pintype "unspecified"))
      (node (ref "CN14") (pin "3") (pinfunction "3_3") (pintype "unspecified"))
      (node (ref "CN14") (pin "4") (pinfunction "4_4") (pintype "unspecified"))
      (node (ref "CN2") (pin "1") (pinfunction "1_1") (pintype "unspecified"))
      (node (ref "CN2") (pin "4") (pinfunction "4_4") (pintype "unspecified"))
      (node (ref "CN2") (pin "5") (pinfunction "5_5") (pintype "unspecified"))
      (node (ref "CN3") (pin "1") (pinfunction "1_1") (pintype "unspecified"))
      (node (ref "CN3") (pin "4") (pinfunction "4_4") (pintype "unspecified"))
      (node (ref "CN3") (pin "5") (pinfunction "5_5") (pintype "unspecified"))
      (node (ref "CN4") (pin "1") (pinfunction "1_1") (pintype "unspecified"))
      (node (ref "CN4") (pin "4") (pinfunction "4_4") (pintype "unspecified"))
      (node (ref "CN4") (pin "5") (pinfunction "5_5") (pintype "unspecified"))
      (node (ref "CN5") (pin "1") (pinfunction "1_1") (pintype "unspecified"))
      (node (ref "CN5") (pin "4") (pinfunction "4_4") (pintype "unspecified"))
      (node (ref "CN5") (pin "5") (pinfunction "5_5") (pintype "unspecified"))
      (node (ref "CN6") (pin "3") (pinfunction "3_3") (pintype "unspecified"))
      (node (ref "CN6") (pin "4") (pinfunction "4_4") (pintype "unspecified"))
      (node (ref "CN7") (pin "3") (pinfunction "3_3") (pintype "unspecified"))
      (node (ref "CN7") (pin "4") (pinfunction "4_4") (pintype "unspecified"))
      (node (ref "CN8") (pin "3") (pinfunction "3_3") (pintype "unspecified"))
      (node (ref "CN8") (pin "4") (pinfunction "4_4") (pintype "unspecified"))
      (node (ref "CN9") (pin "3") (pinfunction "3_3") (pintype "unspecified"))
      (node (ref "CN9") (pin "4") (pinfunction "4_4") (pintype "unspecified"))
      (node (ref "D1") (pin "3") (pinfunction "A_3") (pintype "unspecified"))
      (node (ref "D2") (pin "3") (pinfunction "A_3") (pintype "unspecified"))
      (node (ref "D4") (pin "2") (pinfunction "A_2") (pintype "unspecified"))
      (node (ref "D5") (pin "2") (pinfunction "A_2") (pintype "unspecified"))
      (node (ref "D6") (pin "1") (pinfunction "1_1") (pintype "input"))
      (node (ref "H1") (pin "1") (pinfunction "1_1") (pintype "unspecified"))
      (node (ref "H2") (pin "1") (pinfunction "1_1") (pintype "unspecified"))
      (node (ref "H3") (pin "1") (pinfunction "1_1") (pintype "unspecified"))
      (node (ref "H4") (pin "3") (pinfunction "3_3") (pintype "unspecified"))
      (node (ref "LED1") (pin "1") (pinfunction "GND_1") (pintype "unspecified"))
      (node (ref "LED2") (pin "2") (pinfunction "-_2") (pintype "unspecified"))
      (node (ref "LED3") (pin "2") (pinfunction "-_2") (pintype "unspecified"))
      (node (ref "LED4") (pin "2") (pinfunction "-_2") (pintype "unspecified"))
      (node (ref "LED5") (pin "2") (pinfunction "-_2") (pintype "unspecified"))
      (node (ref "Q1") (pin "2") (pinfunction "E_2") (pintype "unspecified"))
      (node (ref "Q2") (pin "2") (pinfunction "E_2") (pintype "unspecified"))
      (node (ref "R13") (pin "1") (pinfunction "1_1") (pintype "input"))
      (node (ref "R15") (pin "1") (pinfunction "1_1") (pintype "input"))
      (node (ref "R22") (pin "1") (pinfunction "1_1") (pintype "input"))
      (node (ref "R4") (pin "2") (pinfunction "2_2") (pintype "input"))
      (node (ref "SW1") (pin "1") (pinfunction "1_1") (pintype "input"))
      (node (ref "U1") (pin "12") (pinfunction "VSSA/VREF-_12") (pintype "unspecified"))
      (node (ref "U1") (pin "18") (pinfunction "VSS_18") (pintype "unspecified"))
      (node (ref "U1") (pin "31") (pinfunction "VSS_31") (pintype "unspecified"))
      (node (ref "U1") (pin "47") (pinfunction "VSS_47") (pintype "unspecified"))
      (node (ref "U1") (pin "63") (pinfunction "VSS_63") (pintype "unspecified"))
      (node (ref "U2") (pin "1") (pinfunction "1_1") (pintype "unspecified"))
      (node (ref "U3") (pin "1") (pinfunction "1_1") (pintype "unspecified"))
      (node (ref "U4") (pin "2") (pinfunction "GND_2") (pintype "input"))
      (node (ref "U4") (pin "8") (pinfunction "STB_8") (pintype "input"))
      (node (ref "U4") (pin "9") (pinfunction "EP_9") (pintype "input"))
      (node (ref "U5") (pin "2") (pinfunction "GND_2") (pintype "input"))
      (node (ref "U5") (pin "8") (pinfunction "STB_8") (pintype "input"))
      (node (ref "U5") (pin "9") (pinfunction "EP_9") (pintype "input"))
      (node (ref "U6") (pin "3") (pinfunction "GND_3") (pintype "unspecified"))
      (node (ref "U7") (pin "6") (pinfunction "GND_6") (pintype "unspecified"))
      (node (ref "U7") (pin "9") (pinfunction "PowerPAD_9") (pintype "unspecified"))
      (node (ref "U8") (pin "6") (pinfunction "GND_6") (pintype "unspecified"))
      (node (ref "U8") (pin "9") (pinfunction "PowerPAD_9") (pintype "unspecified"))
      (node (ref "U9") (pin "1") (pinfunction "ADJ(GND)_1") (pintype "unspecified"))
      (node (ref "USB1") (pin "1") (pinfunction "EP_1") (pintype "input"))
      (node (ref "USB1") (pin "2") (pinfunction "EP_2") (pintype "input"))
      (node (ref "USB1") (pin "3") (pinfunction "EP_3") (pintype "input"))
      (node (ref "USB1") (pin "4") (pinfunction "EP_4") (pintype "input"))
      (node (ref "USB1") (pin "A1") (pinfunction "GND_A1") (pintype "input"))
      (node (ref "USB1") (pin "A12") (pinfunction "GND_A12") (pintype "input"))
      (node (ref "USB1") (pin "B1") (pinfunction "GND_B1") (pintype "input"))
      (node (ref "USB1") (pin "B12") (pinfunction "GND_B12") (pintype "input"))
      (node (ref "USB2") (pin "1") (pinfunction "EP_1") (pintype "input"))
      (node (ref "USB2") (pin "2") (pinfunction "EP_2") (pintype "input"))
      (node (ref "USB2") (pin "3") (pinfunction "EP_3") (pintype "input"))
      (node (ref "USB2") (pin "4") (pinfunction "EP_4") (pintype "input"))
      (node (ref "USB2") (pin "A1") (pinfunction "GND_A1") (pintype "input"))
      (node (ref "USB2") (pin "A12") (pinfunction "GND_A12") (pintype "input"))
      (node (ref "USB2") (pin "B1") (pinfunction "GND_B1") (pintype "input"))
      (node (ref "USB2") (pin "B12") (pinfunction "GND_B12") (pintype "input"))
      (node (ref "X1") (pin "2") (pinfunction "GND_2") (pintype "unspecified"))
      (node (ref "X1") (pin "4") (pinfunction "GND_4") (pintype "unspecified"))
    )
    (net (code "42") (name "Net-(CN5-Pad2)") (class "Default")
      (node (ref "CN5") (pin "2") (pinfunction "2_2") (pintype "unspecified"))
      (node (ref "R2") (pin "2") (pinfunction "2_2") (pintype "input"))
    )
    (net (code "43") (name "Net-(CN5-Pad3)") (class "Default")
      (node (ref "CN5") (pin "3") (pinfunction "3_3") (pintype "unspecified"))
      (node (ref "R3") (pin "2") (pinfunction "2_2") (pintype "input"))
    )
    (net (code "44") (name "Net-(D3-A)") (class "Default")
      (node (ref "BUZZER1") (pin "2") (pinfunction "2_2") (pintype "input"))
      (node (ref "D3") (pin "2") (pinfunction "A_2") (pintype "unspecified"))
      (node (ref "Q1") (pin "3") (pinfunction "C_3") (pintype "unspecified"))
    )
    (net (code "45") (name "Net-(D4-K)") (class "Default")
      (node (ref "C20") (pin "2") (pinfunction "2_2") (pintype "input"))
      (node (ref "D4") (pin "1") (pinfunction "K_1") (pintype "unspecified"))
      (node (ref "L1") (pin "1") (pinfunction "1_1") (pintype "unspecified"))
      (node (ref "U7") (pin "8") (pinfunction "PH_8") (pintype "unspecified"))
    )
    (net (code "46") (name "Net-(D5-K)") (class "Default")
      (node (ref "C24") (pin "2") (pinfunction "2_2") (pintype "input"))
      (node (ref "D5") (pin "1") (pinfunction "K_1") (pintype "unspecified"))
      (node (ref "L2") (pin "1") (pinfunction "1_1") (pintype "unspecified"))
      (node (ref "U8") (pin "8") (pinfunction "PH_8") (pintype "unspecified"))
    )
    (net (code "47") (name "Net-(H4-Pad1)") (class "Default")
      (node (ref "H4") (pin "1") (pinfunction "1_1") (pintype "unspecified"))
      (node (ref "R20") (pin "1") (pinfunction "1_1") (pintype "input"))
    )
    (net (code "48") (name "Net-(LED2-+)") (class "Default")
      (node (ref "LED2") (pin "1") (pinfunction "+_1") (pintype "unspecified"))
      (node (ref "R16") (pin "1") (pinfunction "1_1") (pintype "input"))
    )
    (net (code "49") (name "Net-(LED3-+)") (class "Default")
      (node (ref "LED3") (pin "1") (pinfunction "+_1") (pintype "unspecified"))
      (node (ref "R17") (pin "1") (pinfunction "1_1") (pintype "input"))
    )
    (net (code "50") (name "Net-(LED4-+)") (class "Default")
      (node (ref "LED4") (pin "1") (pinfunction "+_1") (pintype "unspecified"))
      (node (ref "R18") (pin "1") (pinfunction "1_1") (pintype "input"))
    )
    (net (code "51") (name "Net-(LED5-+)") (class "Default")
      (node (ref "LED5") (pin "1") (pinfunction "+_1") (pintype "unspecified"))
      (node (ref "R19") (pin "1") (pinfunction "1_1") (pintype "input"))
    )
    (net (code "52") (name "Net-(Q1-B)") (class "Default")
      (node (ref "Q1") (pin "1") (pinfunction "B_1") (pintype "unspecified"))
      (node (ref "R11") (pin "2") (pinfunction "2_2") (pintype "input"))
    )
    (net (code "53") (name "Net-(Q2-B)") (class "Default")
      (node (ref "Q2") (pin "1") (pinfunction "B_1") (pintype "unspecified"))
      (node (ref "R20") (pin "2") (pinfunction "2_2") (pintype "input"))
    )
    (net (code "54") (name "Net-(Q3-G)") (class "Default")
      (node (ref "Q3") (pin "4") (pinfunction "G_4") (pintype "unspecified"))
      (node (ref "R22") (pin "2") (pinfunction "2_2") (pintype "input"))
    )
    (net (code "55") (name "Net-(U7-BOOT)") (class "Default")
      (node (ref "C20") (pin "1") (pinfunction "1_1") (pintype "input"))
      (node (ref "U7") (pin "1") (pinfunction "BOOT_1") (pintype "unspecified"))
    )
    (net (code "56") (name "Net-(U7-VSENSE)") (class "Default")
      (node (ref "R12") (pin "1") (pinfunction "1_1") (pintype "input"))
      (node (ref "R13") (pin "2") (pinfunction "2_2") (pintype "input"))
      (node (ref "U7") (pin "4") (pinfunction "VSENSE_4") (pintype "unspecified"))
    )
    (net (code "57") (name "Net-(U8-BOOT)") (class "Default")
      (node (ref "C24") (pin "1") (pinfunction "1_1") (pintype "input"))
      (node (ref "U8") (pin "1") (pinfunction "BOOT_1") (pintype "unspecified"))
    )
    (net (code "58") (name "Net-(U8-VSENSE)") (class "Default")
      (node (ref "R14") (pin "1") (pinfunction "1_1") (pintype "input"))
      (node (ref "R15") (pin "2") (pinfunction "2_2") (pintype "input"))
      (node (ref "U8") (pin "4") (pinfunction "VSENSE_4") (pintype "unspecified"))
    )
    (net (code "59") (name "VCC") (class "Default")
      (node (ref "C18") (pin "2") (pinfunction "2_2") (pintype "input"))
      (node (ref "C19") (pin "2") (pinfunction "2_2") (pintype "input"))
      (node (ref "C22") (pin "2") (pinfunction "2_2") (pintype "input"))
      (node (ref "C23") (pin "2") (pinfunction "2_2") (pintype "input"))
      (node (ref "Q3") (pin "1") (pinfunction "S_1") (pintype "unspecified"))
      (node (ref "Q3") (pin "2") (pinfunction "S_2") (pintype "unspecified"))
      (node (ref "Q3") (pin "3") (pinfunction "S_3") (pintype "unspecified"))
      (node (ref "R16") (pin "2") (pinfunction "2_2") (pintype "input"))
      (node (ref "U7") (pin "7") (pinfunction "VIN_7") (pintype "unspecified"))
      (node (ref "U8") (pin "7") (pinfunction "VIN_7") (pintype "unspecified"))
    )
    (net (code "60") (name "VCC3V3") (class "Default")
      (node (ref "BUZZER1") (pin "1") (pinfunction "+_1") (pintype "input"))
      (node (ref "C13") (pin "1") (pinfunction "1_1") (pintype "input"))
      (node (ref "C15") (pin "1") (pinfunction "1_1") (pintype "input"))
      (node (ref "C16") (pin "2") (pinfunction "2_2") (pintype "input"))
      (node (ref "C17") (pin "2") (pinfunction "2_2") (pintype "input"))
      (node (ref "C26") (pin "1") (pinfunction "1_1") (pintype "input"))
      (node (ref "C3") (pin "1") (pinfunction "1_1") (pintype "input"))
      (node (ref "C4") (pin "2") (pinfunction "2_2") (pintype "input"))
      (node (ref "C5") (pin "2") (pinfunction "2_2") (pintype "input"))
      (node (ref "C6") (pin "2") (pinfunction "2_2") (pintype "input"))
      (node (ref "C7") (pin "2") (pinfunction "2_2") (pintype "input"))
      (node (ref "C8") (pin "2") (pinfunction "2_2") (pintype "input"))
      (node (ref "C9") (pin "2") (pinfunction "2_2") (pintype "input"))
      (node (ref "D3") (pin "1") (pinfunction "K_1") (pintype "unspecified"))
      (node (ref "LED1") (pin "3") (pinfunction "VDD_3") (pintype "unspecified"))
      (node (ref "R1") (pin "2") (pinfunction "2_2") (pintype "input"))
      (node (ref "R19") (pin "2") (pinfunction "2_2") (pintype "input"))
      (node (ref "R21") (pin "2") (pinfunction "2_2") (pintype "input"))
      (node (ref "SW2") (pin "1") (pinfunction "1_1") (pintype "input"))
      (node (ref "U1") (pin "1") (pinfunction "VBAT_1") (pintype "unspecified"))
      (node (ref "U1") (pin "13") (pinfunction "VDDA/VREF+_13") (pintype "unspecified"))
      (node (ref "U1") (pin "19") (pinfunction "VDD_19") (pintype "unspecified"))
      (node (ref "U1") (pin "32") (pinfunction "VDD_32") (pintype "unspecified"))
      (node (ref "U1") (pin "48") (pinfunction "VDD_48") (pintype "unspecified"))
      (node (ref "U1") (pin "64") (pinfunction "VDD_64") (pintype "unspecified"))
      (node (ref "U4") (pin "5") (pinfunction "VIO_5") (pintype "input"))
      (node (ref "U5") (pin "5") (pinfunction "VIO_5") (pintype "input"))
      (node (ref "U6") (pin "5") (pinfunction "VCC_5") (pintype "unspecified"))
      (node (ref "U6") (pin "8") (pinfunction "V3_8") (pintype "unspecified"))
      (node (ref "U9") (pin "2") (pinfunction "VOUT(TAB)_2") (pintype "unspecified"))
    )
    (net (code "61") (name "unconnected-(BUZZER1-Pad3)") (class "Default")
      (node (ref "BUZZER1") (pin "3") (pinfunction "3_3") (pintype "input+no_connect"))
    )
    (net (code "62") (name "unconnected-(BUZZER1-Pad4)") (class "Default")
      (node (ref "BUZZER1") (pin "4") (pinfunction "4_4") (pintype "input+no_connect"))
    )
    (net (code "63") (name "unconnected-(LED1-DO-Pad4)") (class "Default")
      (node (ref "LED1") (pin "4") (pinfunction "DO_4") (pintype "unspecified+no_connect"))
    )
    (net (code "64") (name "unconnected-(U1-PA4-Pad20)") (class "Default")
      (node (ref "U1") (pin "20") (pinfunction "PA4_20") (pintype "unspecified"))
    )
    (net (code "65") (name "unconnected-(U1-PA5-Pad21)") (class "Default")
      (node (ref "U1") (pin "21") (pinfunction "PA5_21") (pintype "unspecified"))
    )
    (net (code "66") (name "unconnected-(U1-PA6-Pad22)") (class "Default")
      (node (ref "U1") (pin "22") (pinfunction "PA6_22") (pintype "unspecified"))
    )
    (net (code "67") (name "unconnected-(U1-PA7-Pad23)") (class "Default")
      (node (ref "U1") (pin "23") (pinfunction "PA7_23") (pintype "unspecified"))
    )
    (net (code "68") (name "unconnected-(U1-PA8-Pad41)") (class "Default")
      (node (ref "U1") (pin "41") (pinfunction "PA8_41") (pintype "unspecified"))
    )
    (net (code "69") (name "unconnected-(U1-PB0-Pad26)") (class "Default")
      (node (ref "U1") (pin "26") (pinfunction "PB0_26") (pintype "unspecified"))
    )
    (net (code "70") (name "unconnected-(U1-PB1-Pad27)") (class "Default")
      (node (ref "U1") (pin "27") (pinfunction "PB1_27") (pintype "unspecified"))
    )
    (net (code "71") (name "unconnected-(U1-PB2-Pad28)") (class "Default")
      (node (ref "U1") (pin "28") (pinfunction "PB2_28") (pintype "unspecified"))
    )
    (net (code "72") (name "unconnected-(U1-PB3-Pad55)") (class "Default")
      (node (ref "U1") (pin "55") (pinfunction "PB3_55") (pintype "unspecified"))
    )
    (net (code "73") (name "unconnected-(U1-PB4-Pad56)") (class "Default")
      (node (ref "U1") (pin "56") (pinfunction "PB4_56") (pintype "unspecified"))
    )
    (net (code "74") (name "unconnected-(U1-PB5-Pad57)") (class "Default")
      (node (ref "U1") (pin "57") (pinfunction "PB5_57") (pintype "unspecified"))
    )
    (net (code "75") (name "unconnected-(U1-PB6-Pad58)") (class "Default")
      (node (ref "U1") (pin "58") (pinfunction "PB6_58") (pintype "unspecified"))
    )
    (net (code "76") (name "unconnected-(U1-PB7-Pad59)") (class "Default")
      (node (ref "U1") (pin "59") (pinfunction "PB7_59") (pintype "unspecified"))
    )
    (net (code "77") (name "unconnected-(U1-PC0-Pad8)") (class "Default")
      (node (ref "U1") (pin "8") (pinfunction "PC0_8") (pintype "unspecified"))
    )
    (net (code "78") (name "unconnected-(U1-PC1-Pad9)") (class "Default")
      (node (ref "U1") (pin "9") (pinfunction "PC1_9") (pintype "unspecified"))
    )
    (net (code "79") (name "unconnected-(U1-PC2-Pad10)") (class "Default")
      (node (ref "U1") (pin "10") (pinfunction "PC2_10") (pintype "unspecified"))
    )
    (net (code "80") (name "unconnected-(U1-PC3-Pad11)") (class "Default")
      (node (ref "U1") (pin "11") (pinfunction "PC3_11") (pintype "unspecified"))
    )
    (net (code "81") (name "unconnected-(U1-PC4-Pad24)") (class "Default")
      (node (ref "U1") (pin "24") (pinfunction "PC4_24") (pintype "unspecified"))
    )
    (net (code "82") (name "unconnected-(U1-PC6-Pad37)") (class "Default")
      (node (ref "U1") (pin "37") (pinfunction "PC6_37") (pintype "unspecified"))
    )
    (net (code "83") (name "unconnected-(U1-PC7-Pad38)") (class "Default")
      (node (ref "U1") (pin "38") (pinfunction "PC7_38") (pintype "unspecified"))
    )
    (net (code "84") (name "unconnected-(U1-PC8-Pad39)") (class "Default")
      (node (ref "U1") (pin "39") (pinfunction "PC8_39") (pintype "unspecified"))
    )
    (net (code "85") (name "unconnected-(U1-PC11-Pad52)") (class "Default")
      (node (ref "U1") (pin "52") (pinfunction "PC11_52") (pintype "unspecified"))
    )
    (net (code "86") (name "unconnected-(U1-PC13-Pad2)") (class "Default")
      (node (ref "U1") (pin "2") (pinfunction "PC13_2") (pintype "unspecified"))
    )
    (net (code "87") (name "unconnected-(U1-PD2-Pad54)") (class "Default")
      (node (ref "U1") (pin "54") (pinfunction "PD2_54") (pintype "unspecified"))
    )
    (net (code "88") (name "unconnected-(U6-RTS#-Pad4)") (class "Default")
      (node (ref "U6") (pin "4") (pinfunction "RTS#_4") (pintype "unspecified+no_connect"))
    )
    (net (code "89") (name "unconnected-(U7-ENA-Pad5)") (class "Default")
      (node (ref "U7") (pin "5") (pinfunction "ENA_5") (pintype "unspecified+no_connect"))
    )
    (net (code "90") (name "unconnected-(U7-NC-Pad2)") (class "Default")
      (node (ref "U7") (pin "2") (pinfunction "NC_2") (pintype "unspecified+no_connect"))
    )
    (net (code "91") (name "unconnected-(U7-NC-Pad3)") (class "Default")
      (node (ref "U7") (pin "3") (pinfunction "NC_3") (pintype "unspecified+no_connect"))
    )
    (net (code "92") (name "unconnected-(U8-ENA-Pad5)") (class "Default")
      (node (ref "U8") (pin "5") (pinfunction "ENA_5") (pintype "unspecified+no_connect"))
    )
    (net (code "93") (name "unconnected-(U8-NC-Pad2)") (class "Default")
      (node (ref "U8") (pin "2") (pinfunction "NC_2") (pintype "unspecified+no_connect"))
    )
    (net (code "94") (name "unconnected-(U8-NC-Pad3)") (class "Default")
      (node (ref "U8") (pin "3") (pinfunction "NC_3") (pintype "unspecified+no_connect"))
    )
    (net (code "95") (name "unconnected-(USB1-CC1-PadA5)") (class "Default")
      (node (ref "USB1") (pin "A5") (pinfunction "CC1_A5") (pintype "input+no_connect"))
    )
    (net (code "96") (name "unconnected-(USB1-CC2-PadB5)") (class "Default")
      (node (ref "USB1") (pin "B5") (pinfunction "CC2_B5") (pintype "input+no_connect"))
    )
    (net (code "97") (name "unconnected-(USB1-SBUS1-PadA8)") (class "Default")
      (node (ref "USB1") (pin "A8") (pinfunction "SBUS1_A8") (pintype "input+no_connect"))
    )
    (net (code "98") (name "unconnected-(USB1-SBUS2-PadB8)") (class "Default")
      (node (ref "USB1") (pin "B8") (pinfunction "SBUS2_B8") (pintype "input+no_connect"))
    )
    (net (code "99") (name "unconnected-(USB2-CC1-PadA5)") (class "Default")
      (node (ref "USB2") (pin "A5") (pinfunction "CC1_A5") (pintype "input+no_connect"))
    )
    (net (code "100") (name "unconnected-(USB2-CC2-PadB5)") (class "Default")
      (node (ref "USB2") (pin "B5") (pinfunction "CC2_B5") (pintype "input+no_connect"))
    )
    (net (code "101") (name "unconnected-(USB2-SBUS1-PadA8)") (class "Default")
      (node (ref "USB2") (pin "A8") (pinfunction "SBUS1_A8") (pintype "input+no_connect"))
    )
    (net (code "102") (name "unconnected-(USB2-SBUS2-PadB8)") (class "Default")
      (node (ref "USB2") (pin "B8") (pinfunction "SBUS2_B8") (pintype "input+no_connect"))
    )
  )
)
